# Battery_Protection.net
KiCad netlist of a schematic drawn in Altium Designer
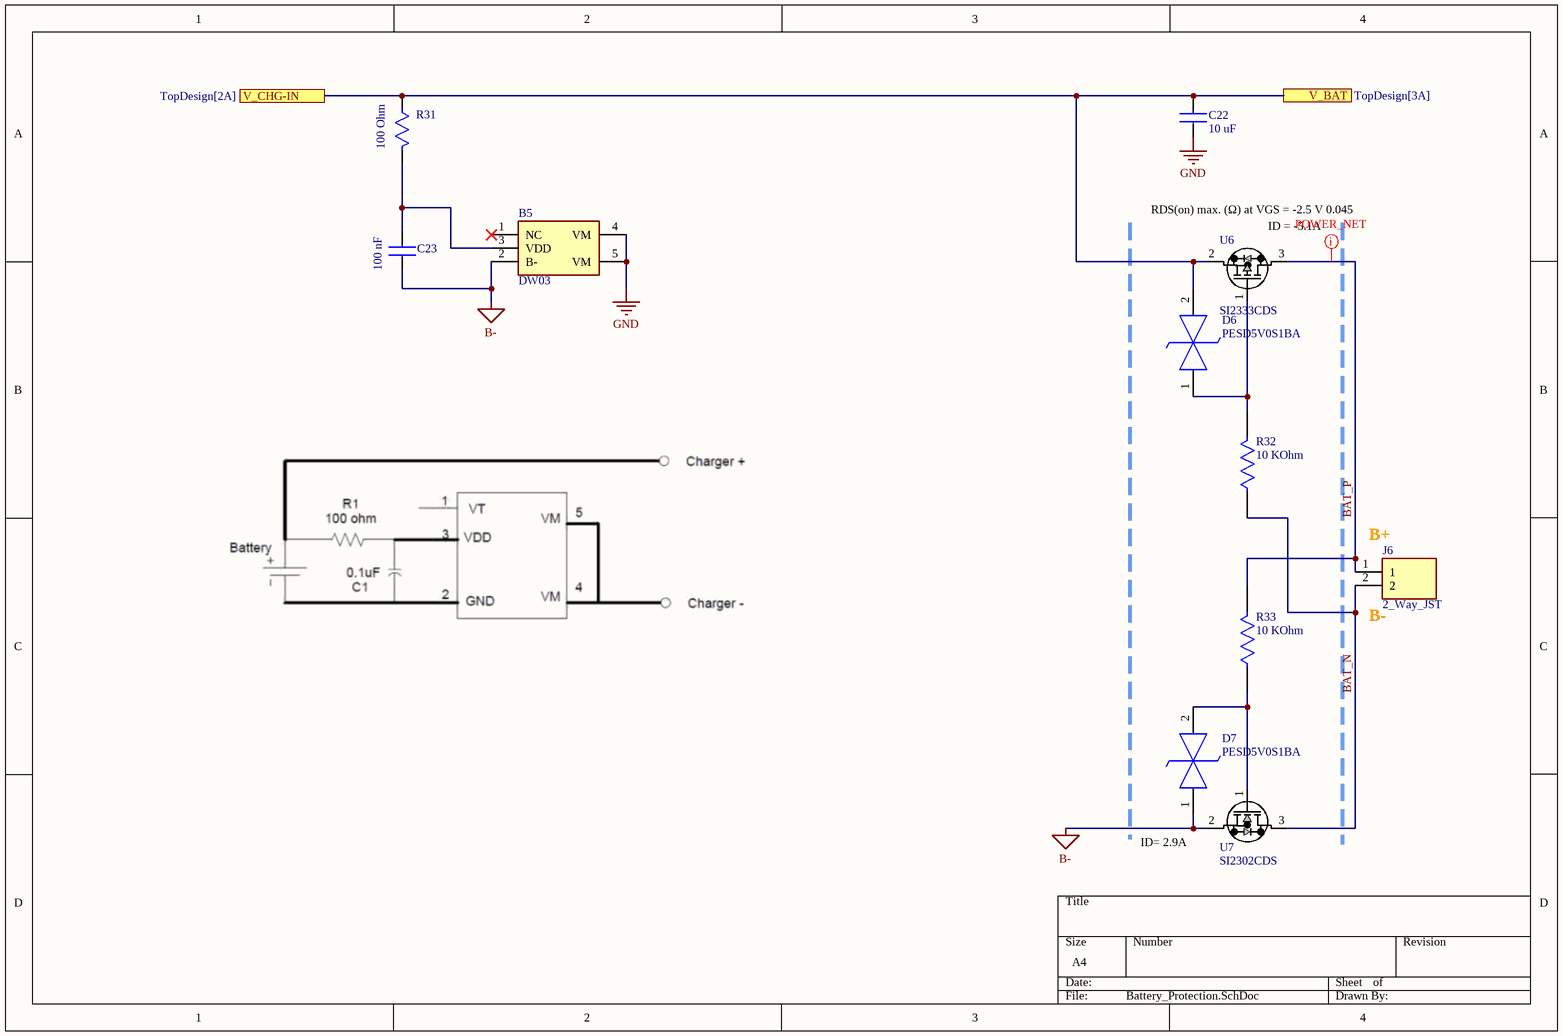
[diagram p0: Battery_Protection.SchDoc]

(export (version "E")
  (design (tool "Eeschema 10.0.6"))
  (components
    (comp (ref "B5")
      (value "DW03")
      (footprint "DW03")
      (description "2K 256X8 1.8V Ser.EEPROM,24AA02E48T-I/OT")
      (libsource (lib "Aptinex_devices") (part "DW03"))
    )
    (comp (ref "C22")
      (value "10 uF")
      (footprint "CAP_0603")
      (description "Cap Ceramic 1uF 10V X5R 10% Pad SMD 0402 85C T/R")
      (fields
        (field (name "MANUFACTURER_PART_NUMBER") "CL05A105KP5NNNC")
        (field (name "MOUSER PART NUMBER") "187-CL05A105KP5NNNC")
      )
      (libsource (lib "Aptinex_discrete") (part "Cap_SMD_New"))
    )
    (comp (ref "C23")
      (value "100 nF")
      (footprint "CAP_0603")
      (description "Cap Ceramic 1uF 10V X5R 10% Pad SMD 0402 85C T/R")
      (fields
        (field (name "MANUFACTURER_PART_NUMBER") "CL05A105KP5NNNC")
        (field (name "MOUSER PART NUMBER") "187-CL05A105KP5NNNC")
      )
      (libsource (lib "Aptinex_discrete") (part "Cap_SMD_New"))
    )
    (comp (ref "D6")
      (value "PESD5V0S1BA")
      (footprint "TVS_SOD-323")
      (description "Diode ESD (Bi-directional)")
      (fields
        (field (name "MANUFACTURER_PART_NUMBER") "PESD12VL1BA,115")
        (field (name "MOUSER PART NUMBER") "771-PESD12VL1BA-T/R")
      )
      (libsource (lib "Aptinex_discrete") (part "TVS_Diode_Bi-Direcctional"))
    )
    (comp (ref "D7")
      (value "PESD5V0S1BA")
      (footprint "TVS_SOD-323")
      (description "Diode ESD (Bi-directional)")
      (fields
        (field (name "MANUFACTURER_PART_NUMBER") "PESD12VL1BA,115")
        (field (name "MOUSER PART NUMBER") "771-PESD12VL1BA-T/R")
      )
      (libsource (lib "Aptinex_discrete") (part "TVS_Diode_Bi-Direcctional"))
    )
    (comp (ref "J6")
      (value "2_Way_JST")
      (footprint "2_Way_JST_Connector")
      (description "Connector Header Through Hole 2 position 0.098 (2.50mm)")
      (fields (field (name "MF") "JST Sales") (field (name "MP") "B2B-XH-A(LF)(SN)"))
      (libsource (lib "Aptinex_connectors") (part "2_Way_JST_Connector"))
    )
    (comp (ref "R31")
      (value "100 Ohm")
      (footprint "Res_0603")
      (description "SMD Resistor")
      (fields (field (name "MP") "RC0805FR-07330RL") (field (name "MF") "Yageo"))
      (libsource (lib "") (part "Res smd_1"))
    )
    (comp (ref "R32")
      (value "10 KOhm")
      (footprint "Res_0603")
      (description "SMD Resistor")
      (fields (field (name "MP") "RC0805FR-07330RL") (field (name "MF") "Yageo"))
      (libsource (lib "Aptinex_discrete") (part "Res smd"))
    )
    (comp (ref "R33")
      (value "10 KOhm")
      (footprint "Res_0603")
      (description "SMD Resistor")
      (fields (field (name "MP") "RC0805FR-07330RL") (field (name "MF") "Yageo"))
      (libsource (lib "Aptinex_discrete") (part "Res smd"))
    )
    (comp (ref "U6")
      (value "SI2333CDS")
      (footprint "SOT-23")
      (description "P-Channel  MOSFET Vds=12V ,RDS(on)=35mOhm .  at VGS = 4.5 V")
      (libsource (lib "Aptinex_discrete") (part "SI2333CDS"))
    )
    (comp (ref "U7")
      (value "SI2302CDS")
      (footprint "SOT-23")
      (description "N-Channel  MOSFET Vds=20V ,RDS(on)=57mOhm .  at VGS = 4.5 V")
      (libsource (lib "Aptinex_discrete") (part "SI2302CDS"))
    )
  )
  (nets
    (net (code "1") (name "/BAT_N") (class "Default")
      (node (ref "J6") (pin "2") (pinfunction "2_2") (pintype "passive"))
      (node (ref "R32") (pin "1") (pinfunction "1_1") (pintype "passive"))
      (node (ref "U7") (pin "3") (pinfunction "D_3") (pintype "passive"))
    )
    (net (code "2") (name "/BAT_P") (class "Default")
      (node (ref "J6") (pin "1") (pinfunction "1_1") (pintype "passive"))
      (node (ref "R33") (pin "2") (pinfunction "2_2") (pintype "passive"))
      (node (ref "U6") (pin "3") (pinfunction "D_3") (pintype "passive"))
    )
    (net (code "3") (name "/V_BAT") (class "Default")
      (node (ref "C22") (pin "2") (pinfunction "2_2") (pintype "passive"))
      (node (ref "D6") (pin "2") (pinfunction "K2_2") (pintype "passive"))
      (node (ref "R31") (pin "2") (pinfunction "2_2") (pintype "passive"))
      (node (ref "U6") (pin "2") (pinfunction "S_2") (pintype "passive"))
    )
    (net (code "4") (name "B-") (class "Default")
      (node (ref "B5") (pin "2") (pinfunction "B-_2") (pintype "passive"))
      (node (ref "C23") (pin "1") (pinfunction "1_1") (pintype "passive"))
      (node (ref "D7") (pin "1") (pinfunction "K1_1") (pintype "passive"))
      (node (ref "U7") (pin "2") (pinfunction "S_2") (pintype "passive"))
    )
    (net (code "5") (name "GND") (class "Default")
      (node (ref "B5") (pin "4") (pinfunction "VM_4") (pintype "passive"))
      (node (ref "B5") (pin "5") (pinfunction "VM_5") (pintype "passive"))
      (node (ref "C22") (pin "1") (pinfunction "1_1") (pintype "passive"))
    )
    (net (code "6") (name "Net-(B5-VDD)") (class "Default")
      (node (ref "B5") (pin "3") (pinfunction "VDD_3") (pintype "passive"))
      (node (ref "C23") (pin "2") (pinfunction "2_2") (pintype "passive"))
      (node (ref "R31") (pin "1") (pinfunction "1_1") (pintype "passive"))
    )
    (net (code "7") (name "Net-(D6-K1)") (class "Default")
      (node (ref "D6") (pin "1") (pinfunction "K1_1") (pintype "passive"))
      (node (ref "R32") (pin "2") (pinfunction "2_2") (pintype "passive"))
      (node (ref "U6") (pin "1") (pinfunction "G_1") (pintype "passive"))
    )
    (net (code "8") (name "Net-(D7-K2)") (class "Default")
      (node (ref "D7") (pin "2") (pinfunction "K2_2") (pintype "passive"))
      (node (ref "R33") (pin "1") (pinfunction "1_1") (pintype "passive"))
      (node (ref "U7") (pin "1") (pinfunction "G_1") (pintype "passive"))
    )
    (net (code "9") (name "unconnected-(B5-NC-Pad1)") (class "Default")
      (node (ref "B5") (pin "1") (pinfunction "NC_1") (pintype "passive+no_connect"))
    )
  )
)
